# LCDTFT_RTP_DRV_XPT2046.net
KiCad netlist of a schematic drawn in Altium Designer
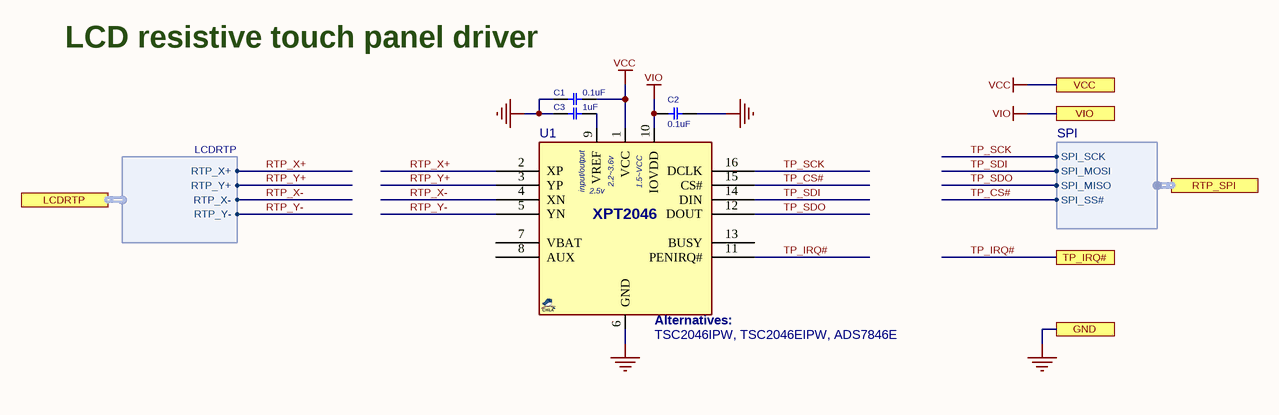
[diagram p0: LCDTFT_RTP_DRV_XPT2046.SchDoc]

(export (version "E")
  (design (tool "Eeschema 10.0.6"))
  (components
    (comp (ref "C1")
      (value "0.1uF")
      (footprint "C0402")
      (description "CAP, MLCC")
      (fields (field (name "MANF_P#") "GRM155R71H104KE14D") (field (name "MANF") "Murata"))
      (libsource (lib "passive_smd") (part "CAP_SMD_MLCC"))
    )
    (comp (ref "C2")
      (value "0.1uF")
      (footprint "C0402")
      (description "CAP, MLCC")
      (fields (field (name "MANF_P#") "GRM155R71H104KE14D") (field (name "MANF") "Murata"))
      (libsource (lib "passive_smd") (part "CAP_SMD_MLCC"))
    )
    (comp (ref "C3")
      (value "1uF")
      (footprint "C0402")
      (description "CAP, MLCC")
      (fields (field (name "MANF_P#") "CL05A105KO5NNND") (field (name "MANF") "Samsung"))
      (libsource (lib "passive_smd") (part "CAP_SMD_MLCC"))
    )
    (comp (ref "U1")
      (value "XPT2046")
      (footprint "SOG65_16")
      (description "LCD, Touch screen controller, resistive, 4-wire")
      (fields (field (name "MANF") "XPT"))
      (libsource (lib "lcd_resistive_touch_driver") (part "XPT2046_TSSOP16"))
    )
  )
  (nets
    (net (code "3") (name "/RTP_X+") (class "Default")
      (node (ref "U1") (pin "2") (pinfunction "XP_2") (pintype "passive"))
    )
    (net (code "4") (name "/RTP_X-") (class "Default")
      (node (ref "U1") (pin "4") (pinfunction "XN_4") (pintype "passive"))
    )
    (net (code "5") (name "/RTP_Y+") (class "Default")
      (node (ref "U1") (pin "3") (pinfunction "YP_3") (pintype "passive"))
    )
    (net (code "6") (name "/RTP_Y-") (class "Default")
      (node (ref "U1") (pin "5") (pinfunction "YN_5") (pintype "passive"))
    )
    (net (code "7") (name "/TP_CS#") (class "Default")
      (node (ref "U1") (pin "15") (pinfunction "CS#_15") (pintype "passive"))
    )
    (net (code "8") (name "/TP_IRQ#") (class "Default")
      (node (ref "U1") (pin "11") (pinfunction "PENIRQ#_11") (pintype "passive"))
    )
    (net (code "9") (name "/TP_SCK") (class "Default")
      (node (ref "U1") (pin "16") (pinfunction "DCLK_16") (pintype "passive"))
    )
    (net (code "10") (name "/TP_SDI") (class "Default")
      (node (ref "U1") (pin "14") (pinfunction "DIN_14") (pintype "passive"))
    )
    (net (code "11") (name "/TP_SDO") (class "Default")
      (node (ref "U1") (pin "12") (pinfunction "DOUT_12") (pintype "passive"))
    )
    (net (code "14") (name "GND") (class "Default")
      (node (ref "C1") (pin "2") (pinfunction "2_2") (pintype "passive"))
      (node (ref "C2") (pin "1") (pinfunction "1_1") (pintype "passive"))
      (node (ref "C3") (pin "2") (pinfunction "2_2") (pintype "passive"))
      (node (ref "U1") (pin "6") (pinfunction "GND_6") (pintype "passive"))
    )
    (net (code "15") (name "Net-(U1-VREF)") (class "Default")
      (node (ref "C3") (pin "1") (pinfunction "1_1") (pintype "passive"))
      (node (ref "U1") (pin "9") (pinfunction "VREF_9") (pintype "passive"))
    )
    (net (code "16") (name "VCC") (class "Default")
      (node (ref "C1") (pin "1") (pinfunction "1_1") (pintype "passive"))
      (node (ref "U1") (pin "1") (pinfunction "VCC_1") (pintype "passive"))
    )
    (net (code "17") (name "VIO") (class "Default")
      (node (ref "C2") (pin "2") (pinfunction "2_2") (pintype "passive"))
      (node (ref "U1") (pin "10") (pinfunction "IOVDD_10") (pintype "passive"))
    )
    (net (code "18") (name "unconnected-(U1-AUX-Pad8)") (class "Default")
      (node (ref "U1") (pin "8") (pinfunction "AUX_8") (pintype "passive"))
    )
    (net (code "19") (name "unconnected-(U1-BUSY-Pad13)") (class "Default")
      (node (ref "U1") (pin "13") (pinfunction "BUSY_13") (pintype "passive"))
    )
    (net (code "20") (name "unconnected-(U1-VBAT-Pad7)") (class "Default")
      (node (ref "U1") (pin "7") (pinfunction "VBAT_7") (pintype "passive"))
    )
  )
)
